# 014_TTL_inverter.net
KiCad netlist of a schematic drawn in Altium Designer
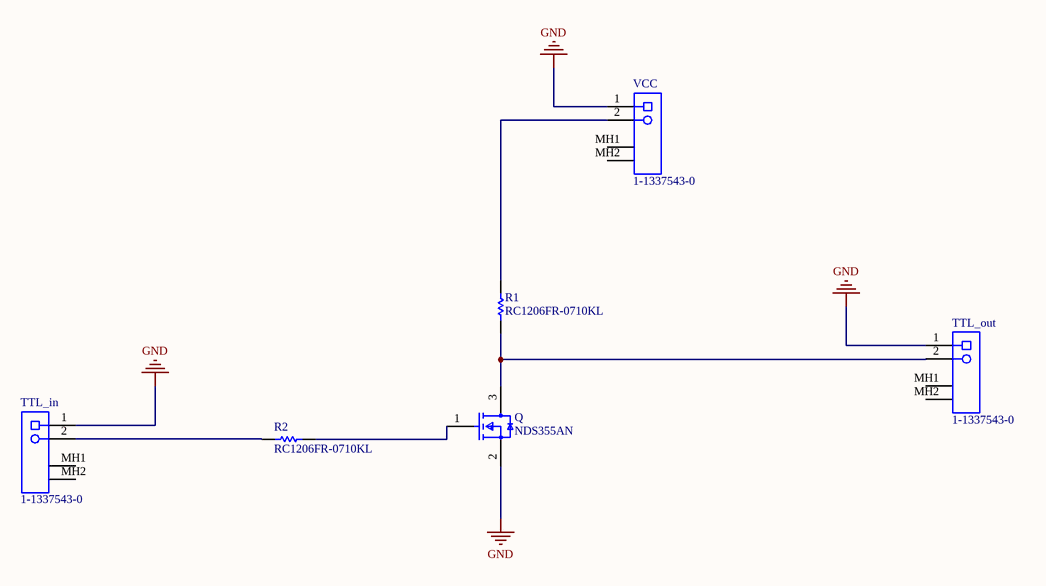
[diagram p0: 014_TTL_inverter.SchDoc]

(export (version "E")
  (design (tool "Eeschema 10.0.6"))
  (components
    (comp (ref "Q")
      (value "NDS355AN")
      (footprint "FP-527AG-01-IPC_C")
      (description "MOSFET N-CH 30V 1.7A SSOT3")
      (fields
        (field (name "OCTOPART") "https://octopart.com/nds355an-on+semiconductor-84330922")
        (field (name "MANUFACTURER") "ON Semiconductor")
      )
      (libsource (lib "Altium Content Vault") (part "3b9c635fedb024a5347a57b145af9cc"))
    )
    (comp (ref "R1")
      (value "RC1206FR-0710KL")
      (footprint "RESC3116X65X40ML10T20")
      (description "Chip Resistor, 10 KOhm, +/- 1%, 0.25 W, -55 to 155 degC, 1206 (3216 Metric), RoHS, Tape and Reel")
      (fields (field (name "TOLERANCE") "1%") (field (name "MANUFACTURER") "Yageo"))
      (libsource (lib "Altium Content Vault") (part "RES-2"))
    )
    (comp (ref "R2")
      (value "RC1206FR-0710KL")
      (footprint "RESC3116X65X40ML10T20")
      (description "Chip Resistor, 10 KOhm, +/- 1%, 0.25 W, -55 to 155 degC, 1206 (3216 Metric), RoHS, Tape and Reel")
      (fields (field (name "TOLERANCE") "1%") (field (name "MANUFACTURER") "Yageo"))
      (libsource (lib "Altium Content Vault") (part "RES-2"))
    )
    (comp (ref "TTL_in")
      (value "1-1337543-0")
      (footprint "TECO-1-1337543-0_V")
      (fields (field (name "MANUFACTURER") "TE Connectivity"))
      (libsource (lib "") (part "CN-1P-F-R2_A_1"))
    )
    (comp (ref "TTL_out")
      (value "1-1337543-0")
      (footprint "TECO-1-1337543-0_V")
      (fields (field (name "MANUFACTURER") "TE Connectivity"))
      (libsource (lib "Altium Content Vault") (part "CN-1P-F-R2_A"))
    )
    (comp (ref "VCC")
      (value "1-1337543-0")
      (footprint "TECO-1-1337543-0_V")
      (fields (field (name "MANUFACTURER") "TE Connectivity"))
      (libsource (lib "Altium Content Vault") (part "CN-1P-F-R2_A"))
    )
  )
  (nets
    (net (code "1") (name "GND") (class "Default")
      (node (ref "Q") (pin "2") (pinfunction "S_2") (pintype "passive"))
      (node (ref "TTL_in") (pin "1") (pinfunction "1_1") (pintype "passive"))
      (node (ref "TTL_out") (pin "1") (pinfunction "1_1") (pintype "passive"))
      (node (ref "VCC") (pin "1") (pinfunction "1_1") (pintype "passive"))
    )
    (net (code "2") (name "Net-(Q-D)") (class "Default")
      (node (ref "Q") (pin "3") (pinfunction "D_3") (pintype "passive"))
      (node (ref "R1") (pin "1") (pinfunction "1_1") (pintype "passive"))
      (node (ref "TTL_out") (pin "2") (pinfunction "2_2") (pintype "passive"))
    )
    (net (code "3") (name "Net-(Q-G)") (class "Default")
      (node (ref "Q") (pin "1") (pinfunction "G_1") (pintype "passive"))
      (node (ref "R2") (pin "1") (pinfunction "1_1") (pintype "passive"))
    )
    (net (code "4") (name "Net-(R1-Pad2)") (class "Default")
      (node (ref "R1") (pin "2") (pinfunction "2_2") (pintype "passive"))
      (node (ref "VCC") (pin "2") (pinfunction "2_2") (pintype "passive"))
    )
    (net (code "5") (name "Net-(R2-Pad2)") (class "Default")
      (node (ref "R2") (pin "2") (pinfunction "2_2") (pintype "passive"))
      (node (ref "TTL_in") (pin "2") (pinfunction "2_2") (pintype "passive"))
    )
    (net (code "6") (name "unconnected-(TTL_in-PadMH1)") (class "Default")
      (node (ref "TTL_in") (pin "MH1") (pinfunction "MH1_MH1") (pintype "passive"))
    )
    (net (code "7") (name "unconnected-(TTL_in-PadMH2)") (class "Default")
      (node (ref "TTL_in") (pin "MH2") (pinfunction "MH2_MH2") (pintype "passive"))
    )
    (net (code "8") (name "unconnected-(TTL_out-PadMH1)") (class "Default")
      (node (ref "TTL_out") (pin "MH1") (pinfunction "MH1_MH1") (pintype "passive"))
    )
    (net (code "9") (name "unconnected-(TTL_out-PadMH2)") (class "Default")
      (node (ref "TTL_out") (pin "MH2") (pinfunction "MH2_MH2") (pintype "passive"))
    )
    (net (code "10") (name "unconnected-(VCC-PadMH1)") (class "Default")
      (node (ref "VCC") (pin "MH1") (pinfunction "MH1_MH1") (pintype "passive"))
    )
    (net (code "11") (name "unconnected-(VCC-PadMH2)") (class "Default")
      (node (ref "VCC") (pin "MH2") (pinfunction "MH2_MH2") (pintype "passive"))
    )
  )
)
